# Final2.net
KiCad netlist of a schematic drawn in EAGLE
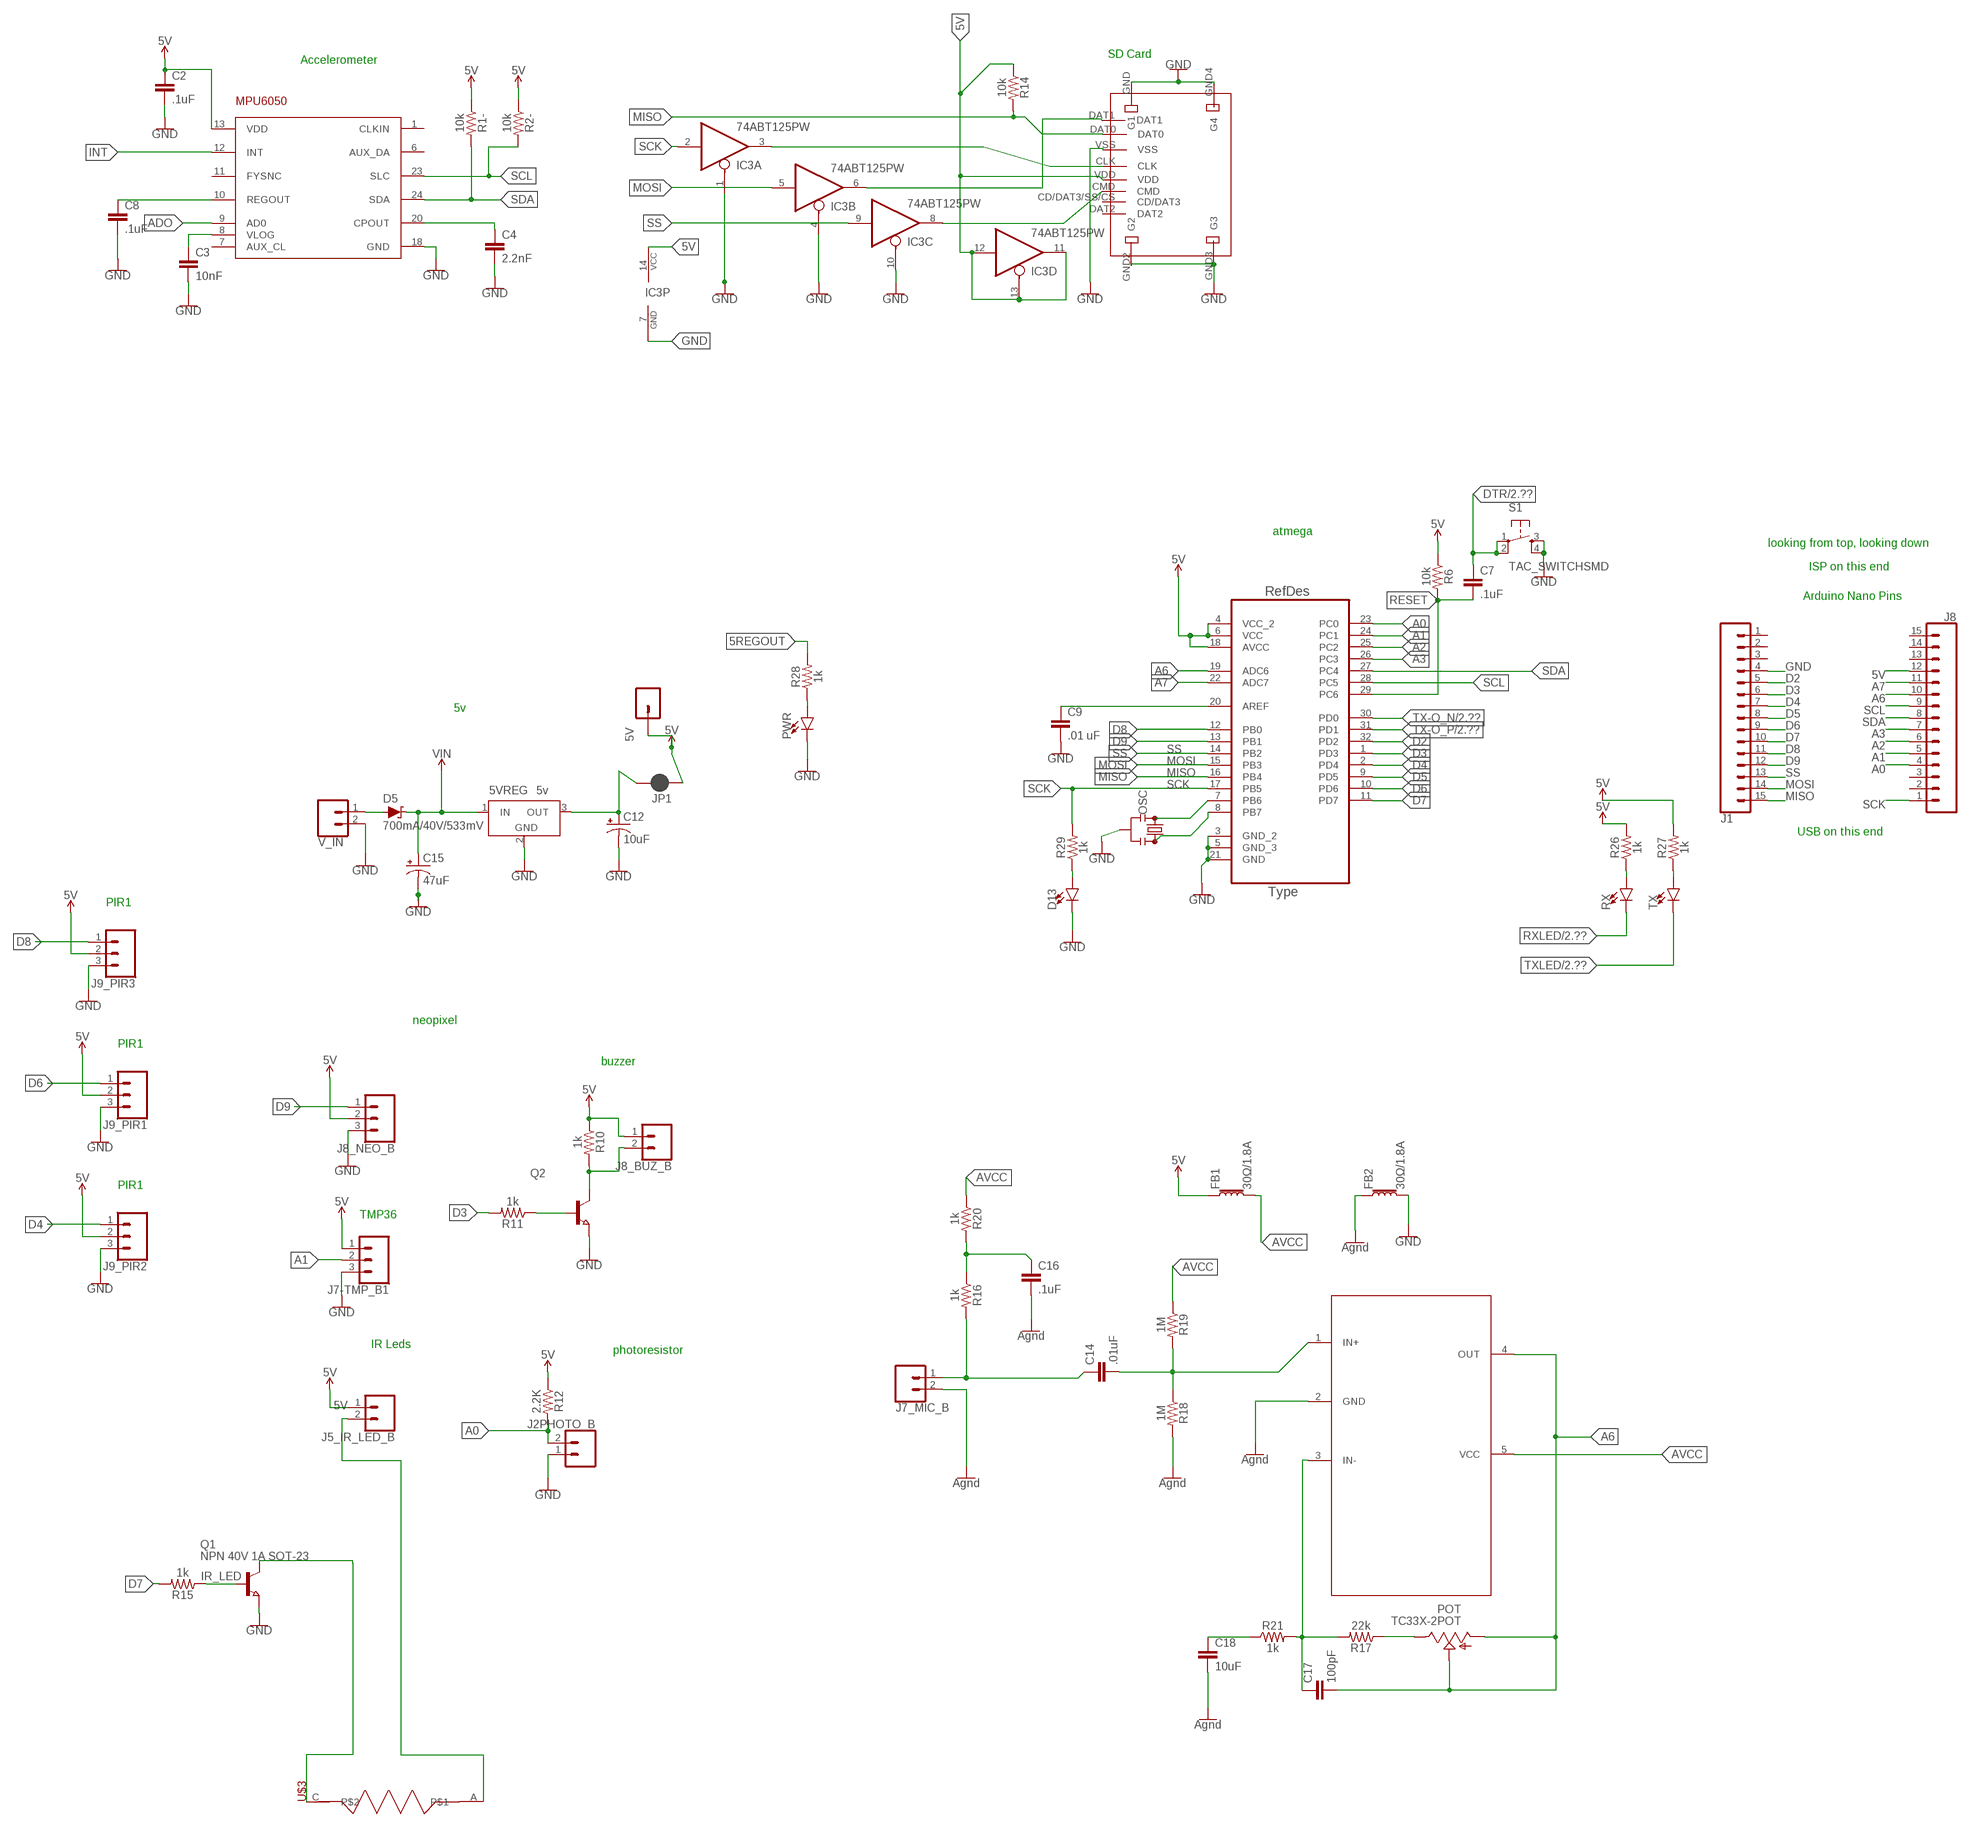
[diagram p0: schematic, sheet 1]
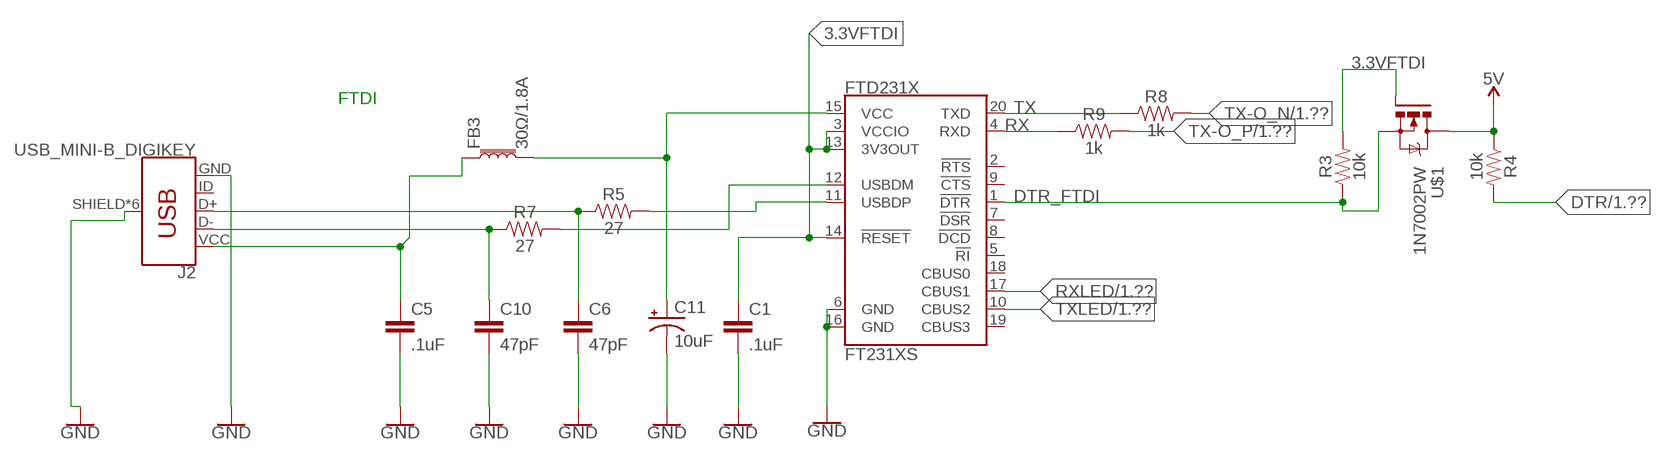
[diagram p1: schematic, sheet 2]

(export (version "E")
  (design (tool "Eeschema 10.0.6"))
  (components
    (comp (ref "5V")
      (value "CONN_01")
      (footprint "eagle-import:1X01")
      (libsource (lib "eagle-import") (part "CONN_01"))
    )
    (comp (ref "5VREG")
      (value "5v")
      (footprint "eagle-import:SOT223")
      (fields (field (name "MPN") "LT1129CST-5#PBF"))
      (libsource (lib "eagle-import") (part "LT1129CST5"))
    )
    (comp (ref "AMP")
      (value "MAX4466KS")
      (footprint "eagle-import:SC70-5")
      (libsource (lib "eagle-import") (part "MAX4466KS"))
    )
    (comp (ref "ATMEGA328P-AU")
      (value "ATMEGA328P-AU")
      (footprint "eagle-import:QFP80P900X900X120-32N")
      (libsource (lib "eagle-import") (part "ATMEGA328P-AU"))
    )
    (comp (ref "C2")
      (value ".1uF")
      (footprint "eagle-import:0402-CAP")
      (libsource (lib "eagle-import") (part ".22UF-CER"))
    )
    (comp (ref "C3")
      (value "10nF")
      (footprint "eagle-import:0402-CAP")
      (libsource (lib "eagle-import") (part ".22UF-CER"))
    )
    (comp (ref "C4")
      (value "2.2nF")
      (footprint "eagle-import:0402-CAP")
      (libsource (lib "eagle-import") (part ".22UF-CER"))
    )
    (comp (ref "C7")
      (value ".1uF")
      (footprint "eagle-import:0402-CAP")
      (libsource (lib "eagle-import") (part ".22UF-CER"))
    )
    (comp (ref "C8")
      (value ".1uF")
      (footprint "eagle-import:0402-CAP")
      (libsource (lib "eagle-import") (part ".22UF-CER"))
    )
    (comp (ref "C9")
      (value ".01 uF")
      (footprint "eagle-import:0402-CAP")
      (libsource (lib "eagle-import") (part ".22UF-CER"))
    )
    (comp (ref "C12")
      (value "10uF")
      (footprint "eagle-import:EIA3216")
      (libsource (lib "eagle-import") (part "10UF-TANT"))
    )
    (comp (ref "C14")
      (value ".01uF")
      (footprint "eagle-import:0402-CAP")
      (libsource (lib "eagle-import") (part ".22UF-CER"))
    )
    (comp (ref "C15")
      (value "47uF")
      (footprint "eagle-import:EIA3216")
      (libsource (lib "eagle-import") (part "10UF-TANT"))
    )
    (comp (ref "C16")
      (value ".1uF")
      (footprint "eagle-import:0402-CAP")
      (libsource (lib "eagle-import") (part ".22UF-CER"))
    )
    (comp (ref "C17")
      (value "100pF")
      (footprint "eagle-import:0402-CAP")
      (libsource (lib "eagle-import") (part ".22UF-CER"))
    )
    (comp (ref "C18")
      (value "10uF")
      (footprint "eagle-import:0402-CAP")
      (libsource (lib "eagle-import") (part ".22UF-CER"))
    )
    (comp (ref "D5")
      (value "700mA/40V/533mV")
      (footprint "eagle-import:SOT23-3")
      (libsource (lib "eagle-import") (part "DIODE-SCHOTTKY-ZLLS500"))
    )
    (comp (ref "D13")
      (value "LED0603")
      (footprint "eagle-import:LED-0603")
      (libsource (lib "eagle-import") (part "LED0603"))
    )
    (comp (ref "FB1")
      (value "30Ω/1.8A")
      (footprint "eagle-import:0603")
      (libsource (lib "eagle-import") (part "FERRITE_BEAD-0603"))
    )
    (comp (ref "FB2")
      (value "30Ω/1.8A")
      (footprint "eagle-import:0603")
      (libsource (lib "eagle-import") (part "FERRITE_BEAD-0603"))
    )
    (comp (ref "IC3")
      (value "74ABT125PW")
      (footprint "eagle-import:TSSOP14")
      (libsource (lib "eagle-import") (part "74125PWABT"))
    )
    (comp (ref "J1")
      (value "CONN_15")
      (footprint "eagle-import:1X15")
      (libsource (lib "eagle-import") (part "CONN_15"))
    )
    (comp (ref "J2PHOTO_B")
      (value "CONN_02LOCK")
      (footprint "eagle-import:1X02_LOCK")
      (libsource (lib "eagle-import") (part "CONN_02LOCK"))
    )
    (comp (ref "J5_IR_LED_B")
      (value "CONN_02LOCK")
      (footprint "eagle-import:1X02_LOCK")
      (libsource (lib "eagle-import") (part "CONN_02LOCK"))
    )
    (comp (ref "J7-TMP_B1")
      (value "CONN_03")
      (footprint "eagle-import:1X03")
      (libsource (lib "eagle-import") (part "CONN_03"))
    )
    (comp (ref "J7_MIC_B")
      (value "CONN_02LOCK")
      (footprint "eagle-import:1X02_LOCK")
      (libsource (lib "eagle-import") (part "CONN_02LOCK"))
    )
    (comp (ref "J8")
      (value "CONN_15")
      (footprint "eagle-import:1X15")
      (libsource (lib "eagle-import") (part "CONN_15"))
    )
    (comp (ref "J8_BUZ_B")
      (value "CONN_02LOCK")
      (footprint "eagle-import:1X02_LOCK")
      (libsource (lib "eagle-import") (part "CONN_02LOCK"))
    )
    (comp (ref "J8_NEO_B")
      (value "CONN_03")
      (footprint "eagle-import:1X03")
      (libsource (lib "eagle-import") (part "CONN_03"))
    )
    (comp (ref "J9_PIR1")
      (value "CONN_03")
      (footprint "eagle-import:1X03")
      (libsource (lib "eagle-import") (part "CONN_03"))
    )
    (comp (ref "J9_PIR2")
      (value "CONN_03")
      (footprint "eagle-import:1X03")
      (libsource (lib "eagle-import") (part "CONN_03"))
    )
    (comp (ref "J9_PIR3")
      (value "CONN_03")
      (footprint "eagle-import:1X03")
      (libsource (lib "eagle-import") (part "CONN_03"))
    )
    (comp (ref "JP1")
      (value "JUMPER-SMT_2_NC_PASTE")
      (footprint "eagle-import:SMT-JUMPER_2_NO_SILK")
      (libsource (lib "eagle-import") (part "JUMPER-SMT_2_NC_PASTE"))
    )
    (comp (ref "MPU6050")
      (value "MPU-6050")
      (footprint "eagle-import:QFN24-4X4")
      (libsource (lib "eagle-import") (part "MPU-6050"))
    )
    (comp (ref "OSC")
      (value "RESONATORSMD-3.2X1.3")
      (footprint "eagle-import:RESONATOR-SMD-3.2X1.3")
      (libsource (lib "eagle-import") (part "RESONATORSMD-3.2X1.3"))
    )
    (comp (ref "POT")
      (value "TC33X-2POT")
      (footprint "eagle-import:TC33X-2")
      (libsource (lib "eagle-import") (part "TC33X-2POT"))
    )
    (comp (ref "PWR")
      (value "LED0603")
      (footprint "eagle-import:LED-0603")
      (libsource (lib "eagle-import") (part "LED0603"))
    )
    (comp (ref "Q1")
      (value "NPN 40V 1A SOT-23")
      (footprint "eagle-import:SOT23")
      (libsource (lib "eagle-import") (part "NPN-TRANSISTOR_SOT23"))
    )
    (comp (ref "Q2")
      (value "NPN-TRANSISTOR_SOT23")
      (footprint "eagle-import:SOT23")
      (libsource (lib "eagle-import") (part "NPN-TRANSISTOR_SOT23"))
    )
    (comp (ref "R1-")
      (value "10k")
      (footprint "eagle-import:0603")
      (libsource (lib "eagle-import") (part "0.05OHM-0603-1/5W-1%"))
    )
    (comp (ref "R2-")
      (value "10k")
      (footprint "eagle-import:0603")
      (libsource (lib "eagle-import") (part "0.05OHM-0603-1/5W-1%"))
    )
    (comp (ref "R6")
      (value "10k")
      (footprint "eagle-import:0603")
      (libsource (lib "eagle-import") (part "0.05OHM-0603-1/5W-1%"))
    )
    (comp (ref "R10")
      (value "1k")
      (footprint "eagle-import:0603")
      (libsource (lib "eagle-import") (part "0.05OHM-0603-1/5W-1%"))
    )
    (comp (ref "R11")
      (value "1k")
      (footprint "eagle-import:0603")
      (libsource (lib "eagle-import") (part "0.05OHM-0603-1/5W-1%"))
    )
    (comp (ref "R12")
      (value "2.2K")
      (footprint "eagle-import:0603")
      (libsource (lib "eagle-import") (part "0.05OHM-0603-1/5W-1%"))
    )
    (comp (ref "R14")
      (value "10k")
      (footprint "eagle-import:0603")
      (libsource (lib "eagle-import") (part "0.05OHM-0603-1/5W-1%"))
    )
    (comp (ref "R15")
      (value "1k")
      (footprint "eagle-import:0603")
      (libsource (lib "eagle-import") (part "0.05OHM-0603-1/5W-1%"))
    )
    (comp (ref "R16")
      (value "1k")
      (footprint "eagle-import:0603")
      (libsource (lib "eagle-import") (part "0.05OHM-0603-1/5W-1%"))
    )
    (comp (ref "R17")
      (value "22k")
      (footprint "eagle-import:0603")
      (libsource (lib "eagle-import") (part "0.05OHM-0603-1/5W-1%"))
    )
    (comp (ref "R18")
      (value "1M")
      (footprint "eagle-import:0603")
      (libsource (lib "eagle-import") (part "0.05OHM-0603-1/5W-1%"))
    )
    (comp (ref "R19")
      (value "1M")
      (footprint "eagle-import:0603")
      (libsource (lib "eagle-import") (part "0.05OHM-0603-1/5W-1%"))
    )
    (comp (ref "R20")
      (value "1k")
      (footprint "eagle-import:0603")
      (libsource (lib "eagle-import") (part "0.05OHM-0603-1/5W-1%"))
    )
    (comp (ref "R21")
      (value "1k")
      (footprint "eagle-import:0603")
      (libsource (lib "eagle-import") (part "0.05OHM-0603-1/5W-1%"))
    )
    (comp (ref "R26")
      (value "1k")
      (footprint "eagle-import:0603")
      (libsource (lib "eagle-import") (part "2.2MOHM-1/10W-5%(0603)"))
    )
    (comp (ref "R27")
      (value "1k")
      (footprint "eagle-import:0603")
      (libsource (lib "eagle-import") (part "2.2MOHM-1/10W-5%(0603)"))
    )
    (comp (ref "R28")
      (value "1k")
      (footprint "eagle-import:0603")
      (libsource (lib "eagle-import") (part "2.2MOHM-1/10W-5%(0603)"))
    )
    (comp (ref "R29")
      (value "1k")
      (footprint "eagle-import:0603")
      (libsource (lib "eagle-import") (part "2.2MOHM-1/10W-5%(0603)"))
    )
    (comp (ref "RX")
      (value "LED0603")
      (footprint "eagle-import:LED-0603")
      (libsource (lib "eagle-import") (part "LED0603"))
    )
    (comp (ref "S1")
      (value "TAC_SWITCHSMD")
      (footprint "eagle-import:TACTILE-SWITCH-SMD")
      (libsource (lib "eagle-import") (part "TAC_SWITCHSMD"))
    )
    (comp (ref "TX")
      (value "LED0603")
      (footprint "eagle-import:LED-0603")
      (libsource (lib "eagle-import") (part "LED0603"))
    )
    (comp (ref "U$2")
      (value "WM6698TR-ND_MICROSD")
      (footprint "eagle-import:MICROSD2")
      (libsource (lib "eagle-import") (part "WM6698TR-ND_MICROSD"))
    )
    (comp (ref "U$3")
      (value "47.5 ohm")
      (footprint "eagle-import:RES-1206")
      (libsource (lib "eagle-import") (part "1206RES"))
    )
    (comp (ref "V_IN")
      (value "CONN_02LOCK")
      (footprint "eagle-import:1X02_LOCK")
      (libsource (lib "eagle-import") (part "CONN_02LOCK"))
    )
    (comp (ref "C1")
      (value ".1uF")
      (footprint "eagle-import:0402-CAP")
      (libsource (lib "eagle-import") (part ".22UF-CER"))
    )
    (comp (ref "C5")
      (value ".1uF")
      (footprint "eagle-import:0402-CAP")
      (libsource (lib "eagle-import") (part ".22UF-CER"))
    )
    (comp (ref "C6")
      (value "47pF")
      (footprint "eagle-import:0402-CAP")
      (libsource (lib "eagle-import") (part ".22UF-CER"))
    )
    (comp (ref "C10")
      (value "47pF")
      (footprint "eagle-import:0402-CAP")
      (libsource (lib "eagle-import") (part ".22UF-CER"))
    )
    (comp (ref "C11")
      (value "10uF")
      (footprint "eagle-import:EIA3216")
      (libsource (lib "eagle-import") (part "10UF-TANT"))
    )
    (comp (ref "FB3")
      (value "30Ω/1.8A")
      (footprint "eagle-import:0603")
      (libsource (lib "eagle-import") (part "FERRITE_BEAD-0603"))
    )
    (comp (ref "FTD231X")
      (value "FT231XS")
      (footprint "eagle-import:SSOP20_L")
      (libsource (lib "eagle-import") (part "FT231XS"))
    )
    (comp (ref "J2")
      (value "USB_MINI-B_DIGIKEY")
      (footprint "eagle-import:MICRO-USB-DIGIKEY-FCI2")
      (libsource (lib "eagle-import") (part "USB_MINI-B_DIGIKEY"))
    )
    (comp (ref "R3")
      (value "10k")
      (footprint "eagle-import:0603")
      (libsource (lib "eagle-import") (part "0.05OHM-0603-1/5W-1%"))
    )
    (comp (ref "R4")
      (value "10k")
      (footprint "eagle-import:0603")
      (libsource (lib "eagle-import") (part "0.05OHM-0603-1/5W-1%"))
    )
    (comp (ref "R5")
      (value "27")
      (footprint "eagle-import:0603")
      (libsource (lib "eagle-import") (part "0.05OHM-0603-1/5W-1%"))
    )
    (comp (ref "R7")
      (value "27")
      (footprint "eagle-import:0603")
      (libsource (lib "eagle-import") (part "0.05OHM-0603-1/5W-1%"))
    )
    (comp (ref "R8")
      (value "1k")
      (footprint "eagle-import:0603")
      (libsource (lib "eagle-import") (part "0.05OHM-0603-1/5W-1%"))
    )
    (comp (ref "R9")
      (value "1k")
      (footprint "eagle-import:0603")
      (libsource (lib "eagle-import") (part "0.05OHM-0603-1/5W-1%"))
    )
    (comp (ref "U$1")
      (value "1N7002PW")
      (footprint "eagle-import:SOT323W_INFINEON")
      (libsource (lib "eagle-import") (part "1N7002PW"))
    )
  )
  (nets
    (net (code "1") (name "3.3VFTDI") (class "Default")
      (node (ref "C1") (pin "1") (pinfunction "1_1") (pintype "passive"))
      (node (ref "FTD231X") (pin "13") (pinfunction "3V3OUT_13") (pintype "bidirectional"))
      (node (ref "FTD231X") (pin "14") (pinfunction "~{RESET}_14") (pintype "bidirectional"))
      (node (ref "FTD231X") (pin "3") (pinfunction "VCCIO_3") (pintype "bidirectional"))
      (node (ref "R3") (pin "2") (pinfunction "2_2") (pintype "passive"))
      (node (ref "U$1") (pin "1") (pinfunction "G_1") (pintype "passive"))
    )
    (net (code "2") (name "5REGOUT") (class "Default")
      (node (ref "5VREG") (pin "3") (pinfunction "OUT_3") (pintype "output"))
      (node (ref "C12") (pin "A") (pinfunction "+_A") (pintype "passive"))
      (node (ref "JP1") (pin "P$1") (pinfunction "2_P$1") (pintype "passive"))
      (node (ref "R28") (pin "2") (pinfunction "2_2") (pintype "passive"))
    )
    (net (code "3") (name "5V") (class "Default")
      (node (ref "5V") (pin "1") (pinfunction "1_1") (pintype "passive"))
      (node (ref "ATMEGA328P-AU") (pin "18") (pinfunction "AVCC_18") (pintype "power_in"))
      (node (ref "ATMEGA328P-AU") (pin "4") (pinfunction "VCC_2_4") (pintype "power_in"))
      (node (ref "ATMEGA328P-AU") (pin "6") (pinfunction "VCC_6") (pintype "power_in"))
      (node (ref "C2") (pin "1") (pinfunction "1_1") (pintype "passive"))
      (node (ref "FB1") (pin "1") (pinfunction "1_1") (pintype "passive"))
      (node (ref "IC3") (pin "11") (pinfunction "O_11") (pintype "tri_state"))
      (node (ref "IC3") (pin "12") (pinfunction "I_12") (pintype "input"))
      (node (ref "IC3") (pin "13") (pinfunction "OE_13") (pintype "input"))
      (node (ref "IC3") (pin "14") (pinfunction "VCC_14") (pintype "power_in"))
      (node (ref "J5_IR_LED_B") (pin "1") (pinfunction "1_1") (pintype "passive"))
      (node (ref "J7-TMP_B1") (pin "1") (pinfunction "1_1") (pintype "passive"))
      (node (ref "J8") (pin "12") (pinfunction "12_12") (pintype "passive"))
      (node (ref "J8_BUZ_B") (pin "1") (pinfunction "1_1") (pintype "passive"))
      (node (ref "J8_NEO_B") (pin "2") (pinfunction "2_2") (pintype "passive"))
      (node (ref "J9_PIR1") (pin "2") (pinfunction "2_2") (pintype "passive"))
      (node (ref "J9_PIR2") (pin "2") (pinfunction "2_2") (pintype "passive"))
      (node (ref "J9_PIR3") (pin "2") (pinfunction "2_2") (pintype "passive"))
      (node (ref "JP1") (pin "2") (pinfunction "1_2") (pintype "passive"))
      (node (ref "MPU6050") (pin "13") (pinfunction "VDD_13") (pintype "bidirectional"))
      (node (ref "R1-") (pin "1") (pinfunction "1_1") (pintype "passive"))
      (node (ref "R10") (pin "1") (pinfunction "1_1") (pintype "passive"))
      (node (ref "R12") (pin "1") (pinfunction "1_1") (pintype "passive"))
      (node (ref "R14") (pin "1") (pinfunction "1_1") (pintype "passive"))
      (node (ref "R2-") (pin "1") (pinfunction "1_1") (pintype "passive"))
      (node (ref "R26") (pin "2") (pinfunction "2_2") (pintype "passive"))
      (node (ref "R27") (pin "2") (pinfunction "2_2") (pintype "passive"))
      (node (ref "R4") (pin "1") (pinfunction "1_1") (pintype "passive"))
      (node (ref "R6") (pin "1") (pinfunction "1_1") (pintype "passive"))
      (node (ref "U$1") (pin "3") (pinfunction "D_3") (pintype "passive"))
      (node (ref "U$2") (pin "VDD") (pinfunction "VDD_VDD") (pintype "bidirectional"))
    )
    (net (code "4") (name "A0") (class "Default")
      (node (ref "ATMEGA328P-AU") (pin "23") (pinfunction "PC0_23") (pintype "bidirectional"))
      (node (ref "J2PHOTO_B") (pin "2") (pinfunction "2_2") (pintype "passive"))
      (node (ref "J8") (pin "4") (pinfunction "4_4") (pintype "passive"))
      (node (ref "R12") (pin "2") (pinfunction "2_2") (pintype "passive"))
    )
    (net (code "5") (name "A1") (class "Default")
      (node (ref "ATMEGA328P-AU") (pin "24") (pinfunction "PC1_24") (pintype "bidirectional"))
      (node (ref "J7-TMP_B1") (pin "2") (pinfunction "2_2") (pintype "passive"))
      (node (ref "J8") (pin "5") (pinfunction "5_5") (pintype "passive"))
    )
    (net (code "6") (name "A2") (class "Default")
      (node (ref "ATMEGA328P-AU") (pin "25") (pinfunction "PC2_25") (pintype "bidirectional"))
      (node (ref "J8") (pin "6") (pinfunction "6_6") (pintype "passive"))
    )
    (net (code "7") (name "A3") (class "Default")
      (node (ref "ATMEGA328P-AU") (pin "26") (pinfunction "PC3_26") (pintype "bidirectional"))
      (node (ref "J8") (pin "7") (pinfunction "7_7") (pintype "passive"))
    )
    (net (code "8") (name "A6") (class "Default")
      (node (ref "AMP") (pin "4") (pinfunction "OUT_4") (pintype "bidirectional"))
      (node (ref "ATMEGA328P-AU") (pin "19") (pinfunction "ADC6_19") (pintype "input"))
      (node (ref "C17") (pin "2") (pinfunction "2_2") (pintype "passive"))
      (node (ref "J8") (pin "10") (pinfunction "10_10") (pintype "passive"))
      (node (ref "POT") (pin "2") (pinfunction "2_2") (pintype "passive"))
      (node (ref "POT") (pin "3") (pinfunction "3_3") (pintype "passive"))
    )
    (net (code "9") (name "A7") (class "Default")
      (node (ref "ATMEGA328P-AU") (pin "22") (pinfunction "ADC7_22") (pintype "input"))
      (node (ref "J8") (pin "11") (pinfunction "11_11") (pintype "passive"))
    )
    (net (code "10") (name "ADO") (class "Default")
      (node (ref "MPU6050") (pin "9") (pinfunction "AD0_9") (pintype "bidirectional"))
    )
    (net (code "11") (name "AVCC") (class "Default")
      (node (ref "AMP") (pin "5") (pinfunction "VCC_5") (pintype "bidirectional"))
      (node (ref "FB1") (pin "2") (pinfunction "2_2") (pintype "passive"))
      (node (ref "R19") (pin "1") (pinfunction "1_1") (pintype "passive"))
      (node (ref "R20") (pin "1") (pinfunction "1_1") (pintype "passive"))
    )
    (net (code "12") (name "D2") (class "Default")
      (node (ref "ATMEGA328P-AU") (pin "32") (pinfunction "PD2_32") (pintype "bidirectional"))
      (node (ref "J1") (pin "5") (pinfunction "5_5") (pintype "passive"))
    )
    (net (code "13") (name "D3") (class "Default")
      (node (ref "ATMEGA328P-AU") (pin "1") (pinfunction "PD3_1") (pintype "bidirectional"))
      (node (ref "J1") (pin "6") (pinfunction "6_6") (pintype "passive"))
      (node (ref "R11") (pin "2") (pinfunction "2_2") (pintype "passive"))
    )
    (net (code "14") (name "D4") (class "Default")
      (node (ref "ATMEGA328P-AU") (pin "2") (pinfunction "PD4_2") (pintype "bidirectional"))
      (node (ref "J1") (pin "7") (pinfunction "7_7") (pintype "passive"))
      (node (ref "J9_PIR2") (pin "1") (pinfunction "1_1") (pintype "passive"))
    )
    (net (code "15") (name "D5") (class "Default")
      (node (ref "ATMEGA328P-AU") (pin "9") (pinfunction "PD5_9") (pintype "bidirectional"))
      (node (ref "J1") (pin "8") (pinfunction "8_8") (pintype "passive"))
    )
    (net (code "16") (name "D6") (class "Default")
      (node (ref "ATMEGA328P-AU") (pin "10") (pinfunction "PD6_10") (pintype "bidirectional"))
      (node (ref "J1") (pin "9") (pinfunction "9_9") (pintype "passive"))
      (node (ref "J9_PIR1") (pin "1") (pinfunction "1_1") (pintype "passive"))
    )
    (net (code "17") (name "D7") (class "Default")
      (node (ref "ATMEGA328P-AU") (pin "11") (pinfunction "PD7_11") (pintype "bidirectional"))
      (node (ref "J1") (pin "10") (pinfunction "10_10") (pintype "passive"))
      (node (ref "R15") (pin "2") (pinfunction "2_2") (pintype "passive"))
    )
    (net (code "18") (name "D8") (class "Default")
      (node (ref "ATMEGA328P-AU") (pin "12") (pinfunction "PB0_12") (pintype "bidirectional"))
      (node (ref "J1") (pin "11") (pinfunction "11_11") (pintype "passive"))
      (node (ref "J9_PIR3") (pin "1") (pinfunction "1_1") (pintype "passive"))
    )
    (net (code "19") (name "D9") (class "Default")
      (node (ref "ATMEGA328P-AU") (pin "13") (pinfunction "PB1_13") (pintype "bidirectional"))
      (node (ref "J1") (pin "12") (pinfunction "12_12") (pintype "passive"))
      (node (ref "J8_NEO_B") (pin "1") (pinfunction "1_1") (pintype "passive"))
    )
    (net (code "20") (name "DTR") (class "Default")
      (node (ref "C7") (pin "1") (pinfunction "1_1") (pintype "passive"))
      (node (ref "R4") (pin "2") (pinfunction "2_2") (pintype "passive"))
      (node (ref "S1") (pin "1") (pinfunction "1_1") (pintype "passive"))
      (node (ref "S1") (pin "2") (pinfunction "2_2") (pintype "passive"))
    )
    (net (code "21") (name "DTR_FTDI") (class "Default")
      (node (ref "FTD231X") (pin "1") (pinfunction "~{DTR}_1") (pintype "bidirectional"))
      (node (ref "R3") (pin "1") (pinfunction "1_1") (pintype "passive"))
      (node (ref "U$1") (pin "2") (pinfunction "S_2") (pintype "passive"))
    )
    (net (code "22") (name "GND") (class "Default")
      (node (ref "5VREG") (pin "2") (pinfunction "GND_2") (pintype "power_in"))
      (node (ref "AMP") (pin "2") (pinfunction "GND_2") (pintype "bidirectional"))
      (node (ref "ATMEGA328P-AU") (pin "21") (pinfunction "GND_21") (pintype "passive"))
      (node (ref "ATMEGA328P-AU") (pin "3") (pinfunction "GND_2_3") (pintype "passive"))
      (node (ref "ATMEGA328P-AU") (pin "5") (pinfunction "GND_3_5") (pintype "passive"))
      (node (ref "C1") (pin "2") (pinfunction "2_2") (pintype "passive"))
      (node (ref "C10") (pin "2") (pinfunction "2_2") (pintype "passive"))
      (node (ref "C11") (pin "C") (pinfunction "-_C") (pintype "passive"))
      (node (ref "C12") (pin "C") (pinfunction "-_C") (pintype "passive"))
      (node (ref "C15") (pin "C") (pinfunction "-_C") (pintype "passive"))
      (node (ref "C16") (pin "2") (pinfunction "2_2") (pintype "passive"))
      (node (ref "C18") (pin "2") (pinfunction "2_2") (pintype "passive"))
      (node (ref "C2") (pin "2") (pinfunction "2_2") (pintype "passive"))
      (node (ref "C3") (pin "2") (pinfunction "2_2") (pintype "passive"))
      (node (ref "C4") (pin "2") (pinfunction "2_2") (pintype "passive"))
      (node (ref "C5") (pin "2") (pinfunction "2_2") (pintype "passive"))
      (node (ref "C6") (pin "2") (pinfunction "2_2") (pintype "passive"))
      (node (ref "C8") (pin "2") (pinfunction "2_2") (pintype "passive"))
      (node (ref "C9") (pin "2") (pinfunction "2_2") (pintype "passive"))
      (node (ref "D13") (pin "C") (pinfunction "C_C") (pintype "passive"))
      (node (ref "FB2") (pin "1") (pinfunction "1_1") (pintype "passive"))
      (node (ref "FB2") (pin "2") (pinfunction "2_2") (pintype "passive"))
      (node (ref "FTD231X") (pin "16") (pinfunction "GND_16") (pintype "bidirectional"))
      (node (ref "FTD231X") (pin "6") (pinfunction "GND_6") (pintype "bidirectional"))
      (node (ref "IC3") (pin "1") (pinfunction "OE_1") (pintype "input"))
      (node (ref "IC3") (pin "10") (pinfunction "OE_10") (pintype "input"))
      (node (ref "IC3") (pin "4") (pinfunction "OE_4") (pintype "input"))
      (node (ref "IC3") (pin "7") (pinfunction "GND_7") (pintype "power_in"))
      (node (ref "J1") (pin "4") (pinfunction "4_4") (pintype "passive"))
      (node (ref "J2") (pin "GND") (pinfunction "GND_GND") (pintype "power_in"))
      (node (ref "J2") (pin "SHIELD") (pinfunction "SHIELD_SHIELD") (pintype "bidirectional"))
      (node (ref "J2") (pin "SHIELD1") (pinfunction "SHIELD_SHIELD1") (pintype "bidirectional"))
      (node (ref "J2") (pin "SHIELD2") (pinfunction "SHIELD_SHIELD2") (pintype "bidirectional"))
      (node (ref "J2") (pin "SHIELD3") (pinfunction "SHIELD_SHIELD3") (pintype "bidirectional"))
      (node (ref "J2") (pin "SHIELD4") (pinfunction "SHIELD_SHIELD4") (pintype "bidirectional"))
      (node (ref "J2") (pin "SHIELD5") (pinfunction "SHIELD_SHIELD5") (pintype "bidirectional"))
      (node (ref "J2PHOTO_B") (pin "1") (pinfunction "1_1") (pintype "passive"))
      (node (ref "J7-TMP_B1") (pin "3") (pinfunction "3_3") (pintype "passive"))
      (node (ref "J7_MIC_B") (pin "2") (pinfunction "2_2") (pintype "passive"))
      (node (ref "J8_NEO_B") (pin "3") (pinfunction "3_3") (pintype "passive"))
      (node (ref "J9_PIR1") (pin "3") (pinfunction "3_3") (pintype "passive"))
      (node (ref "J9_PIR2") (pin "3") (pinfunction "3_3") (pintype "passive"))
      (node (ref "J9_PIR3") (pin "3") (pinfunction "3_3") (pintype "passive"))
      (node (ref "MPU6050") (pin "18") (pinfunction "GND_18") (pintype "bidirectional"))
      (node (ref "OSC") (pin "2") (pinfunction "2_2") (pintype "passive"))
      (node (ref "PWR") (pin "C") (pinfunction "C_C") (pintype "passive"))
      (node (ref "Q1") (pin "2") (pinfunction "E_2") (pintype "passive"))
      (node (ref "Q2") (pin "2") (pinfunction "E_2") (pintype "passive"))
      (node (ref "R18") (pin "2") (pinfunction "2_2") (pintype "passive"))
      (node (ref "S1") (pin "3") (pinfunction "3_3") (pintype "passive"))
      (node (ref "S1") (pin "4") (pinfunction "4_4") (pintype "passive"))
      (node (ref "U$2") (pin "GND") (pinfunction "G1_GND") (pintype "bidirectional"))
      (node (ref "U$2") (pin "GND2") (pinfunction "G2_GND2") (pintype "bidirectional"))
      (node (ref "U$2") (pin "GND3") (pinfunction "G3_GND3") (pintype "bidirectional"))
      (node (ref "U$2") (pin "GND4") (pinfunction "G4_GND4") (pintype "bidirectional"))
      (node (ref "U$2") (pin "VSS") (pinfunction "VSS_VSS") (pintype "bidirectional"))
      (node (ref "V_IN") (pin "2") (pinfunction "2_2") (pintype "passive"))
    )
    (net (code "23") (name "INT") (class "Default")
      (node (ref "MPU6050") (pin "12") (pinfunction "INT_12") (pintype "bidirectional"))
    )
    (net (code "24") (name "IR_LED") (class "Default")
      (node (ref "Q1") (pin "1") (pinfunction "B_1") (pintype "passive"))
      (node (ref "R15") (pin "1") (pinfunction "1_1") (pintype "passive"))
    )
    (net (code "25") (name "MISO") (class "Default")
      (node (ref "ATMEGA328P-AU") (pin "16") (pinfunction "PB4_16") (pintype "bidirectional"))
      (node (ref "J1") (pin "15") (pinfunction "15_15") (pintype "passive"))
      (node (ref "R14") (pin "2") (pinfunction "2_2") (pintype "passive"))
      (node (ref "U$2") (pin "DAT0") (pinfunction "DAT0_DAT0") (pintype "bidirectional"))
    )
    (net (code "26") (name "MOSI") (class "Default")
      (node (ref "ATMEGA328P-AU") (pin "15") (pinfunction "PB3_15") (pintype "bidirectional"))
      (node (ref "IC3") (pin "5") (pinfunction "I_5") (pintype "input"))
      (node (ref "J1") (pin "14") (pinfunction "14_14") (pintype "passive"))
    )
    (net (code "27") (name "Net-(AMP-IN+)") (class "Default")
      (node (ref "AMP") (pin "1") (pinfunction "IN+_1") (pintype "bidirectional"))
      (node (ref "C14") (pin "2") (pinfunction "2_2") (pintype "passive"))
      (node (ref "R18") (pin "1") (pinfunction "1_1") (pintype "passive"))
      (node (ref "R19") (pin "2") (pinfunction "2_2") (pintype "passive"))
    )
    (net (code "28") (name "Net-(AMP-IN-)") (class "Default")
      (node (ref "AMP") (pin "3") (pinfunction "IN-_3") (pintype "bidirectional"))
      (node (ref "C17") (pin "1") (pinfunction "1_1") (pintype "passive"))
      (node (ref "R17") (pin "2") (pinfunction "2_2") (pintype "passive"))
      (node (ref "R21") (pin "2") (pinfunction "2_2") (pintype "passive"))
    )
    (net (code "29") (name "Net-(ATMEGA328P-AU-AREF)") (class "Default")
      (node (ref "ATMEGA328P-AU") (pin "20") (pinfunction "AREF_20") (pintype "input"))
      (node (ref "C9") (pin "1") (pinfunction "1_1") (pintype "passive"))
    )
    (net (code "30") (name "Net-(ATMEGA328P-AU-PB6)") (class "Default")
      (node (ref "ATMEGA328P-AU") (pin "7") (pinfunction "PB6_7") (pintype "bidirectional"))
      (node (ref "OSC") (pin "1") (pinfunction "1_1") (pintype "passive"))
    )
    (net (code "31") (name "Net-(ATMEGA328P-AU-PB7)") (class "Default")
      (node (ref "ATMEGA328P-AU") (pin "8") (pinfunction "PB7_8") (pintype "bidirectional"))
      (node (ref "OSC") (pin "3") (pinfunction "3_3") (pintype "passive"))
    )
    (net (code "32") (name "Net-(C6-Pad1)") (class "Default")
      (node (ref "C6") (pin "1") (pinfunction "1_1") (pintype "passive"))
      (node (ref "J2") (pin "D+") (pinfunction "D+_D+") (pintype "bidirectional"))
      (node (ref "R5") (pin "1") (pinfunction "1_1") (pintype "passive"))
    )
    (net (code "33") (name "Net-(C10-Pad1)") (class "Default")
      (node (ref "C10") (pin "1") (pinfunction "1_1") (pintype "passive"))
      (node (ref "J2") (pin "D-") (pinfunction "D-_D-") (pintype "bidirectional"))
      (node (ref "R7") (pin "1") (pinfunction "1_1") (pintype "passive"))
    )
    (net (code "34") (name "Net-(C14-Pad1)") (class "Default")
      (node (ref "C14") (pin "1") (pinfunction "1_1") (pintype "passive"))
      (node (ref "J7_MIC_B") (pin "1") (pinfunction "1_1") (pintype "passive"))
      (node (ref "R16") (pin "2") (pinfunction "2_2") (pintype "passive"))
    )
    (net (code "35") (name "Net-(C16-Pad1)") (class "Default")
      (node (ref "C16") (pin "1") (pinfunction "1_1") (pintype "passive"))
      (node (ref "R16") (pin "1") (pinfunction "1_1") (pintype "passive"))
      (node (ref "R20") (pin "2") (pinfunction "2_2") (pintype "passive"))
    )
    (net (code "36") (name "Net-(C18-Pad1)") (class "Default")
      (node (ref "C18") (pin "1") (pinfunction "1_1") (pintype "passive"))
      (node (ref "R21") (pin "1") (pinfunction "1_1") (pintype "passive"))
    )
    (net (code "37") (name "Net-(D5-A)") (class "Default")
      (node (ref "D5") (pin "1") (pinfunction "A_1") (pintype "passive"))
      (node (ref "V_IN") (pin "1") (pinfunction "1_1") (pintype "passive"))
    )
    (net (code "38") (name "Net-(D13-PadA)") (class "Default")
      (node (ref "D13") (pin "A") (pinfunction "A_A") (pintype "passive"))
      (node (ref "R29") (pin "1") (pinfunction "1_1") (pintype "passive"))
    )
    (net (code "39") (name "Net-(FTD231X-USBDM)") (class "Default")
      (node (ref "FTD231X") (pin "12") (pinfunction "USBDM_12") (pintype "bidirectional"))
      (node (ref "R7") (pin "2") (pinfunction "2_2") (pintype "passive"))
    )
    (net (code "40") (name "Net-(FTD231X-USBDP)") (class "Default")
      (node (ref "FTD231X") (pin "11") (pinfunction "USBDP_11") (pintype "bidirectional"))
      (node (ref "R5") (pin "2") (pinfunction "2_2") (pintype "passive"))
    )
    (net (code "41") (name "Net-(IC3A-O)") (class "Default")
      (node (ref "IC3") (pin "3") (pinfunction "O_3") (pintype "tri_state"))
      (node (ref "U$2") (pin "CLK") (pinfunction "CLK_CLK") (pintype "bidirectional"))
    )
    (net (code "42") (name "Net-(IC3B-O)") (class "Default")
      (node (ref "IC3") (pin "6") (pinfunction "O_6") (pintype "tri_state"))
      (node (ref "U$2") (pin "DAT1") (pinfunction "DAT1_DAT1") (pintype "bidirectional"))
    )
    (net (code "43") (name "Net-(IC3C-O)") (class "Default")
      (node (ref "IC3") (pin "8") (pinfunction "O_8") (pintype "tri_state"))
      (node (ref "U$2") (pin "CMD") (pinfunction "CMD_CMD") (pintype "bidirectional"))
    )
    (net (code "44") (name "Net-(MPU6050-CPOUT)") (class "Default")
      (node (ref "C4") (pin "1") (pinfunction "1_1") (pintype "passive"))
      (node (ref "MPU6050") (pin "20") (pinfunction "CPOUT_20") (pintype "bidirectional"))
    )
    (net (code "45") (name "Net-(MPU6050-REGOUT)") (class "Default")
      (node (ref "C8") (pin "1") (pinfunction "1_1") (pintype "passive"))
      (node (ref "MPU6050") (pin "10") (pinfunction "REGOUT_10") (pintype "bidirectional"))
    )
    (net (code "46") (name "Net-(MPU6050-VLOG)") (class "Default")
      (node (ref "C3") (pin "1") (pinfunction "1_1") (pintype "passive"))
      (node (ref "MPU6050") (pin "8") (pinfunction "VLOG_8") (pintype "bidirectional"))
    )
    (net (code "47") (name "Net-(POT-Pad1)") (class "Default")
      (node (ref "POT") (pin "1") (pinfunction "1_1") (pintype "passive"))
      (node (ref "R17") (pin "1") (pinfunction "1_1") (pintype "passive"))
    )
    (net (code "48") (name "Net-(PWR-PadA)") (class "Default")
      (node (ref "PWR") (pin "A") (pinfunction "A_A") (pintype "passive"))
      (node (ref "R28") (pin "1") (pinfunction "1_1") (pintype "passive"))
    )
    (net (code "49") (name "Net-(Q1-C)") (class "Default")
      (node (ref "Q1") (pin "3") (pinfunction "C_3") (pintype "passive"))
      (node (ref "U$3") (pin "C") (pinfunction "P$2_C") (pintype "bidirectional"))
    )
    (net (code "50") (name "Net-(Q2-B)") (class "Default")
      (node (ref "Q2") (pin "1") (pinfunction "B_1") (pintype "passive"))
      (node (ref "R11") (pin "1") (pinfunction "1_1") (pintype "passive"))
    )
    (net (code "51") (name "Net-(Q2-C)") (class "Default")
      (node (ref "J8_BUZ_B") (pin "2") (pinfunction "2_2") (pintype "passive"))
      (node (ref "Q2") (pin "3") (pinfunction "C_3") (pintype "passive"))
      (node (ref "R10") (pin "2") (pinfunction "2_2") (pintype "passive"))
    )
    (net (code "52") (name "Net-(R26-Pad1)") (class "Default")
      (node (ref "R26") (pin "1") (pinfunction "1_1") (pintype "passive"))
      (node (ref "RX") (pin "A") (pinfunction "A_A") (pintype "passive"))
    )
    (net (code "53") (name "Net-(R27-Pad1)") (class "Default")
      (node (ref "R27") (pin "1") (pinfunction "1_1") (pintype "passive"))
      (node (ref "TX") (pin "A") (pinfunction "A_A") (pintype "passive"))
    )
    (net (code "54") (name "Net-(U$3-P$1)") (class "Default")
      (node (ref "J5_IR_LED_B") (pin "2") (pinfunction "2_2") (pintype "passive"))
      (node (ref "U$3") (pin "A") (pinfunction "P$1_A") (pintype "bidirectional"))
    )
    (net (code "55") (name "RESET") (class "Default")
      (node (ref "ATMEGA328P-AU") (pin "29") (pinfunction "PC6_29") (pintype "bidirectional"))
      (node (ref "C7") (pin "2") (pinfunction "2_2") (pintype "passive"))
      (node (ref "R6") (pin "2") (pinfunction "2_2") (pintype "passive"))
    )
    (net (code "56") (name "RX") (class "Default")
      (node (ref "FTD231X") (pin "4") (pinfunction "RXD_4") (pintype "bidirectional"))
      (node (ref "R9") (pin "1") (pinfunction "1_1") (pintype "passive"))
    )
    (net (code "57") (name "RXLED") (class "Default")
      (node (ref "FTD231X") (pin "17") (pinfunction "CBUS1_17") (pintype "bidirectional"))
      (node (ref "RX") (pin "C") (pinfunction "C_C") (pintype "passive"))
    )
    (net (code "58") (name "SCK") (class "Default")
      (node (ref "ATMEGA328P-AU") (pin "17") (pinfunction "PB5_17") (pintype "bidirectional"))
      (node (ref "IC3") (pin "2") (pinfunction "I_2") (pintype "input"))
      (node (ref "J8") (pin "1") (pinfunction "1_1") (pintype "passive"))
      (node (ref "R29") (pin "2") (pinfunction "2_2") (pintype "passive"))
    )
    (net (code "59") (name "SCL") (class "Default")
      (node (ref "ATMEGA328P-AU") (pin "28") (pinfunction "PC5_28") (pintype "bidirectional"))
      (node (ref "J8") (pin "9") (pinfunction "9_9") (pintype "passive"))
      (node (ref "MPU6050") (pin "23") (pinfunction "SLC_23") (pintype "bidirectional"))
      (node (ref "R2-") (pin "2") (pinfunction "2_2") (pintype "passive"))
    )
    (net (code "60") (name "SDA") (class "Default")
      (node (ref "ATMEGA328P-AU") (pin "27") (pinfunction "PC4_27") (pintype "bidirectional"))
      (node (ref "J8") (pin "8") (pinfunction "8_8") (pintype "passive"))
      (node (ref "MPU6050") (pin "24") (pinfunction "SDA_24") (pintype "bidirectional"))
      (node (ref "R1-") (pin "2") (pinfunction "2_2") (pintype "passive"))
    )
    (net (code "61") (name "SS") (class "Default")
      (node (ref "ATMEGA328P-AU") (pin "14") (pinfunction "PB2_14") (pintype "bidirectional"))
      (node (ref "IC3") (pin "9") (pinfunction "I_9") (pintype "input"))
      (node (ref "J1") (pin "13") (pinfunction "13_13") (pintype "passive"))
    )
    (net (code "62") (name "TX") (class "Default")
      (node (ref "FTD231X") (pin "20") (pinfunction "TXD_20") (pintype "bidirectional"))
      (node (ref "R8") (pin "1") (pinfunction "1_1") (pintype "passive"))
    )
    (net (code "63") (name "TX-O_N") (class "Default")
      (node (ref "ATMEGA328P-AU") (pin "30") (pinfunction "PD0_30") (pintype "bidirectional"))
      (node (ref "R8") (pin "2") (pinfunction "2_2") (pintype "passive"))
    )
    (net (code "64") (name "TX-O_P") (class "Default")
      (node (ref "ATMEGA328P-AU") (pin "31") (pinfunction "PD1_31") (pintype "bidirectional"))
      (node (ref "R9") (pin "2") (pinfunction "2_2") (pintype "passive"))
    )
    (net (code "65") (name "TXLED") (class "Default")
      (node (ref "FTD231X") (pin "10") (pinfunction "CBUS2_10") (pintype "bidirectional"))
      (node (ref "TX") (pin "C") (pinfunction "C_C") (pintype "passive"))
    )
    (net (code "66") (name "VIN") (class "Default")
      (node (ref "5VREG") (pin "1") (pinfunction "IN_1") (pintype "input"))
      (node (ref "C15") (pin "A") (pinfunction "+_A") (pintype "passive"))
      (node (ref "D5") (pin "3") (pinfunction "C_3") (pintype "passive"))
    )
    (net (code "67") (name "VUSB") (class "Default")
      (node (ref "C11") (pin "A") (pinfunction "+_A") (pintype "passive"))
      (node (ref "C5") (pin "1") (pinfunction "1_1") (pintype "passive"))
      (node (ref "FB3") (pin "1") (pinfunction "1_1") (pintype "passive"))
      (node (ref "FB3") (pin "2") (pinfunction "2_2") (pintype "passive"))
      (node (ref "FTD231X") (pin "15") (pinfunction "VCC_15") (pintype "bidirectional"))
      (node (ref "J2") (pin "VCC") (pinfunction "VBUS_VCC") (pintype "power_in"))
    )
    (net (code "68") (name "unconnected-(FTD231X-CBUS0-Pad18)") (class "Default")
      (node (ref "FTD231X") (pin "18") (pinfunction "CBUS0_18") (pintype "bidirectional"))
    )
    (net (code "69") (name "unconnected-(FTD231X-CBUS3-Pad19)") (class "Default")
      (node (ref "FTD231X") (pin "19") (pinfunction "CBUS3_19") (pintype "bidirectional"))
    )
    (net (code "70") (name "unconnected-(FTD231X-~{CTS}-Pad9)") (class "Default")
      (node (ref "FTD231X") (pin "9") (pinfunction "~{CTS}_9") (pintype "bidirectional"))
    )
    (net (code "71") (name "unconnected-(FTD231X-~{DCD}-Pad8)") (class "Default")
      (node (ref "FTD231X") (pin "8") (pinfunction "~{DCD}_8") (pintype "bidirectional"))
    )
    (net (code "72") (name "unconnected-(FTD231X-~{DSR}-Pad7)") (class "Default")
      (node (ref "FTD231X") (pin "7") (pinfunction "~{DSR}_7") (pintype "bidirectional"))
    )
    (net (code "73") (name "unconnected-(FTD231X-~{RI}-Pad5)") (class "Default")
      (node (ref "FTD231X") (pin "5") (pinfunction "~{RI}_5") (pintype "bidirectional"))
    )
    (net (code "74") (name "unconnected-(FTD231X-~{RTS}-Pad2)") (class "Default")
      (node (ref "FTD231X") (pin "2") (pinfunction "~{RTS}_2") (pintype "bidirectional"))
    )
    (net (code "75") (name "unconnected-(J1-Pad1)") (class "Default")
      (node (ref "J1") (pin "1") (pinfunction "1_1") (pintype "passive"))
    )
    (net (code "76") (name "unconnected-(J1-Pad2)") (class "Default")
      (node (ref "J1") (pin "2") (pinfunction "2_2") (pintype "passive"))
    )
    (net (code "77") (name "unconnected-(J1-Pad3)") (class "Default")
      (node (ref "J1") (pin "3") (pinfunction "3_3") (pintype "passive"))
    )
    (net (code "78") (name "unconnected-(J2-PadID)") (class "Default")
      (node (ref "J2") (pin "ID") (pinfunction "ID_ID") (pintype "bidirectional"))
    )
    (net (code "79") (name "unconnected-(J8-Pad2)") (class "Default")
      (node (ref "J8") (pin "2") (pinfunction "2_2") (pintype "passive"))
    )
    (net (code "80") (name "unconnected-(J8-Pad3)") (class "Default")
      (node (ref "J8") (pin "3") (pinfunction "3_3") (pintype "passive"))
    )
    (net (code "81") (name "unconnected-(J8-Pad13)") (class "Default")
      (node (ref "J8") (pin "13") (pinfunction "13_13") (pintype "passive"))
    )
    (net (code "82") (name "unconnected-(J8-Pad14)") (class "Default")
      (node (ref "J8") (pin "14") (pinfunction "14_14") (pintype "passive"))
    )
    (net (code "83") (name "unconnected-(J8-Pad15)") (class "Default")
      (node (ref "J8") (pin "15") (pinfunction "15_15") (pintype "passive"))
    )
    (net (code "84") (name "unconnected-(MPU6050-AUX_CL-Pad7)") (class "Default")
      (node (ref "MPU6050") (pin "7") (pinfunction "AUX_CL_7") (pintype "bidirectional"))
    )
    (net (code "85") (name "unconnected-(MPU6050-AUX_DA-Pad6)") (class "Default")
      (node (ref "MPU6050") (pin "6") (pinfunction "AUX_DA_6") (pintype "bidirectional"))
    )
    (net (code "86") (name "unconnected-(MPU6050-CLKIN-Pad1)") (class "Default")
      (node (ref "MPU6050") (pin "1") (pinfunction "CLKIN_1") (pintype "bidirectional"))
    )
    (net (code "87") (name "unconnected-(MPU6050-FYSNC-Pad11)") (class "Default")
      (node (ref "MPU6050") (pin "11") (pinfunction "FYSNC_11") (pintype "bidirectional"))
    )
    (net (code "88") (name "unconnected-(U$2-CD{slash}DAT3-PadCD{slash}DAT3{slash}SS{slash}CS)") (class "Default")
      (node (ref "U$2") (pin "CD/DAT3/SS/CS") (pinfunction "CD/DAT3_CD/DAT3/SS/CS") (pintype "bidirectional"))
    )
    (net (code "89") (name "unconnected-(U$2-PadDAT2)") (class "Default")
      (node (ref "U$2") (pin "DAT2") (pinfunction "DAT2_DAT2") (pintype "bidirectional"))
    )
  )
)
